# OptoOutput.net
KiCad netlist of a schematic drawn in EAGLE
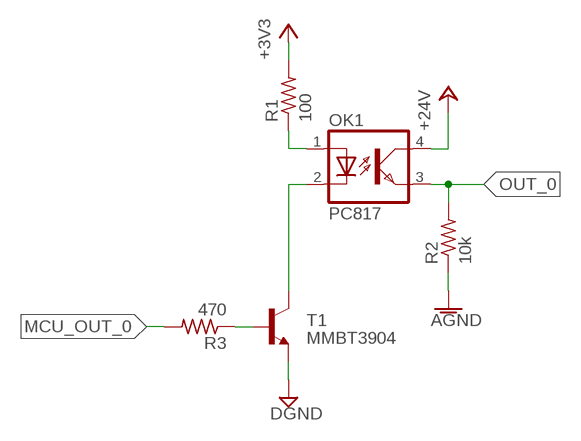
[diagram p0: schematic, sheet 1]

(export (version "E")
  (design (tool "Eeschema 10.0.6"))
  (components
    (comp (ref "OK1")
      (value "PC817")
      (footprint "eagle-import:DIL04")
      (fields (field (name "MPN") "PC817X4J000F"))
      (libsource (lib "eagle-import") (part "PC817"))
    )
    (comp (ref "R1")
      (value "100")
      (footprint "eagle-import:R0402")
      (libsource (lib "eagle-import") (part "R-US_R0402"))
    )
    (comp (ref "R2")
      (value "10k")
      (footprint "eagle-import:R0402")
      (libsource (lib "eagle-import") (part "R-US_R0402"))
    )
    (comp (ref "R3")
      (value "470")
      (footprint "eagle-import:0204_5")
      (libsource (lib "eagle-import") (part "R-US_0204/5"))
    )
    (comp (ref "T1")
      (value "MMBT3904")
      (footprint "eagle-import:SOT23-BEC")
      (libsource (lib "eagle-import") (part "-NPN-SOT23-BECMMBT3904LT1"))
    )
  )
  (nets
    (net (code "1") (name "+3V3") (class "Default")
      (node (ref "R1") (pin "2") (pinfunction "2_2") (pintype "passive"))
    )
    (net (code "2") (name "+24V") (class "Default")
      (node (ref "OK1") (pin "4") (pinfunction "COL_4") (pintype "passive"))
    )
    (net (code "3") (name "AGND") (class "Default")
      (node (ref "R2") (pin "1") (pinfunction "1_1") (pintype "passive"))
    )
    (net (code "4") (name "DGND") (class "Default")
      (node (ref "T1") (pin "E") (pinfunction "E_E") (pintype "passive"))
    )
    (net (code "5") (name "MCU_OUT_0") (class "Default")
      (node (ref "R3") (pin "2") (pinfunction "2_2") (pintype "passive"))
    )
    (net (code "6") (name "Net-(OK1-A)") (class "Default")
      (node (ref "OK1") (pin "1") (pinfunction "A_1") (pintype "passive"))
      (node (ref "R1") (pin "1") (pinfunction "1_1") (pintype "passive"))
    )
    (net (code "7") (name "Net-(OK1-C)") (class "Default")
      (node (ref "OK1") (pin "2") (pinfunction "C_2") (pintype "passive"))
      (node (ref "T1") (pin "C") (pinfunction "C_C") (pintype "passive"))
    )
    (net (code "8") (name "Net-(R3-Pad1)") (class "Default")
      (node (ref "R3") (pin "1") (pinfunction "1_1") (pintype "passive"))
      (node (ref "T1") (pin "B") (pinfunction "B_B") (pintype "passive"))
    )
    (net (code "9") (name "OUT_0") (class "Default")
      (node (ref "OK1") (pin "3") (pinfunction "EMIT_3") (pintype "passive"))
      (node (ref "R2") (pin "2") (pinfunction "2_2") (pintype "passive"))
    )
  )
)
